# W5500_SCH.net
KiCad netlist of a schematic drawn in Altium Designer
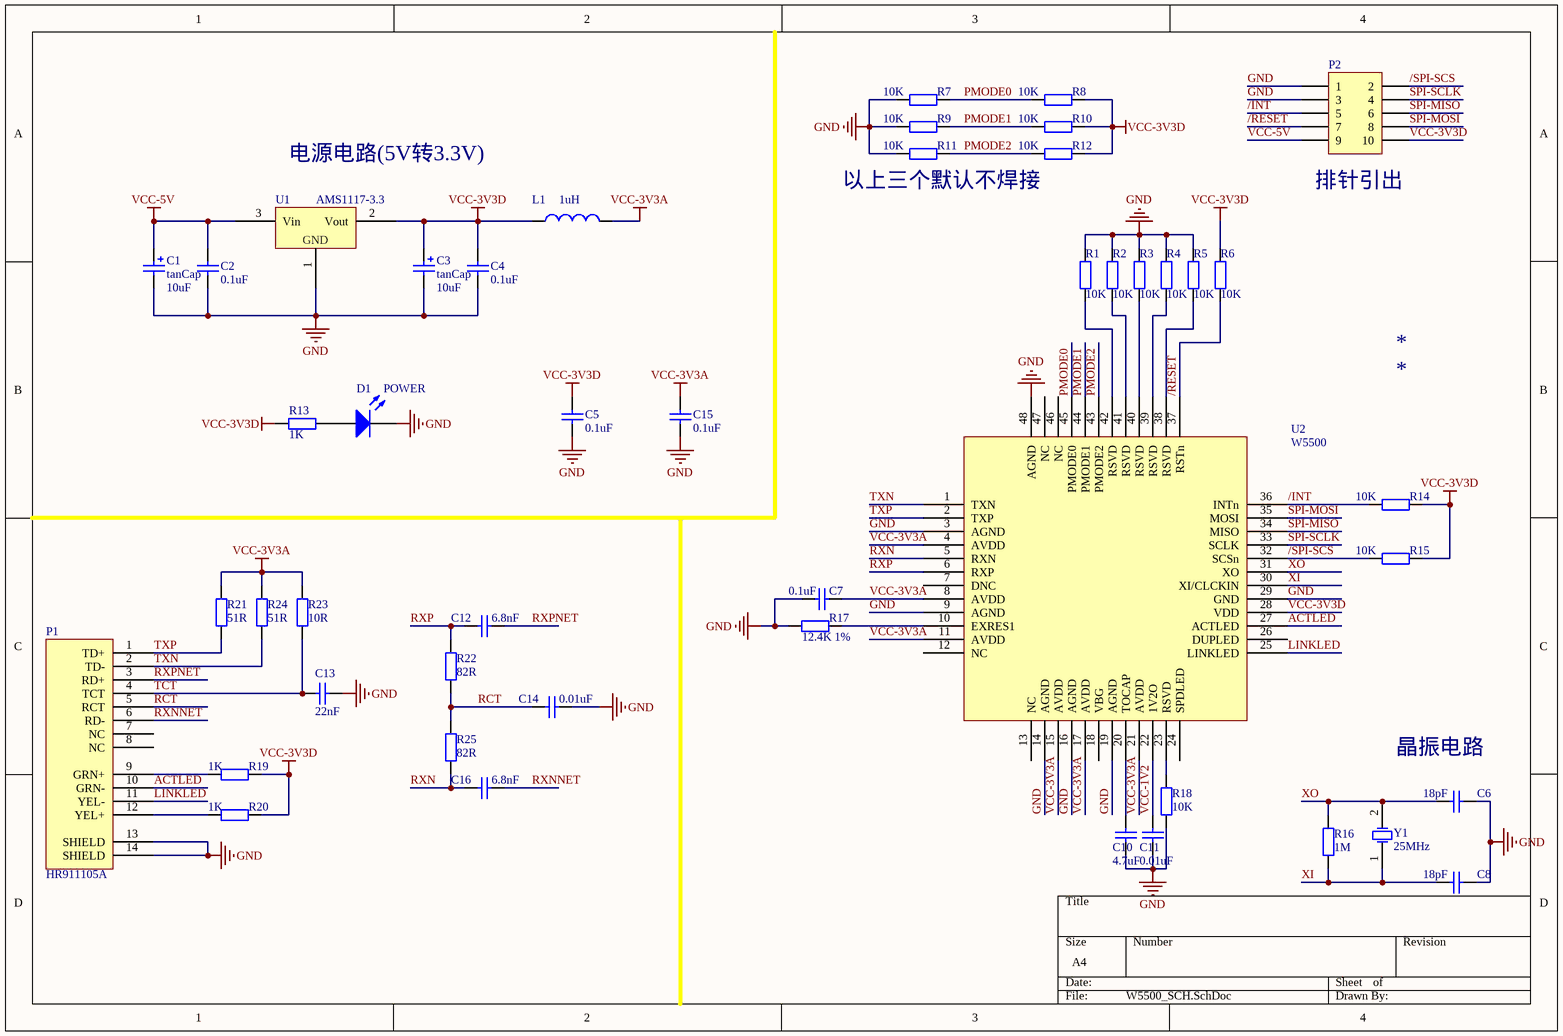
[diagram p0: W5500_SCH.SchDoc]

(export (version "E")
  (design (tool "Eeschema 10.0.6"))
  (components
    (comp (ref "C1")
      (value "tanCap")
      (footprint "C1206")
      (description "Polarized Capacitor (Axial)")
      (fields (field (name "ALTIUM_VALUE") "10uF") (field (name "PUBLISHER") "Altium Limited"))
      (libsource (lib "Miscellaneous Devices") (part "Cap Pol2"))
    )
    (comp (ref "C2")
      (value "0.1uF")
      (footprint "C0805")
      (description "Capacitor")
      (fields (field (name "Comment") "Cap") (field (name "PUBLISHER") "Altium Limited"))
      (libsource (lib "Miscellaneous Devices") (part "Cap"))
    )
    (comp (ref "C3")
      (value "tanCap")
      (footprint "C1206")
      (description "Polarized Capacitor (Axial)")
      (fields (field (name "ALTIUM_VALUE") "10uF") (field (name "PUBLISHER") "Altium Limited"))
      (libsource (lib "Miscellaneous Devices") (part "Cap Pol2"))
    )
    (comp (ref "C4")
      (value "0.1uF")
      (footprint "C0805")
      (description "Capacitor")
      (fields (field (name "Comment") "Cap") (field (name "PUBLISHER") "Altium Limited"))
      (libsource (lib "Miscellaneous Devices") (part "Cap"))
    )
    (comp (ref "C5")
      (value "0.1uF")
      (footprint "C0805")
      (description "Capacitor")
      (fields (field (name "Comment") "Cap") (field (name "PUBLISHER") "Altium Limited"))
      (libsource (lib "Miscellaneous Devices") (part "Cap"))
    )
    (comp (ref "C6")
      (value "18pF")
      (footprint "C0805")
      (description "Capacitor")
      (fields (field (name "Comment") "Cap") (field (name "PUBLISHER") "Altium Limited"))
      (libsource (lib "Miscellaneous Devices") (part "Cap"))
    )
    (comp (ref "C7")
      (value "0.1uF")
      (footprint "C0805")
      (description "Capacitor")
      (fields (field (name "Comment") "Cap") (field (name "PUBLISHER") "Altium Limited"))
      (libsource (lib "Miscellaneous Devices") (part "Cap"))
    )
    (comp (ref "C8")
      (value "18pF")
      (footprint "C0805")
      (description "Capacitor")
      (fields (field (name "Comment") "Cap") (field (name "PUBLISHER") "Altium Limited"))
      (libsource (lib "Miscellaneous Devices") (part "Cap"))
    )
    (comp (ref "C10")
      (value "4.7uF")
      (footprint "C0805")
      (description "Capacitor")
      (fields (field (name "Comment") "Cap") (field (name "PUBLISHER") "Altium Limited"))
      (libsource (lib "Miscellaneous Devices") (part "Cap"))
    )
    (comp (ref "C11")
      (value "0.01uF")
      (footprint "C0805")
      (description "Capacitor")
      (fields (field (name "Comment") "Cap") (field (name "PUBLISHER") "Altium Limited"))
      (libsource (lib "Miscellaneous Devices") (part "Cap"))
    )
    (comp (ref "C12")
      (value "6.8nF")
      (footprint "C0805")
      (description "Capacitor")
      (fields (field (name "Comment") "Cap") (field (name "PUBLISHER") "Altium Limited"))
      (libsource (lib "Miscellaneous Devices") (part "Cap"))
    )
    (comp (ref "C13")
      (value "22nF")
      (footprint "C0805")
      (description "Capacitor")
      (fields (field (name "Comment") "Cap") (field (name "PUBLISHER") "Altium Limited"))
      (libsource (lib "Miscellaneous Devices") (part "Cap"))
    )
    (comp (ref "C14")
      (value "0.01uF")
      (footprint "C0805")
      (description "Capacitor")
      (fields (field (name "Comment") "Cap") (field (name "PUBLISHER") "Altium Limited"))
      (libsource (lib "Miscellaneous Devices") (part "Cap"))
    )
    (comp (ref "C15")
      (value "0.1uF")
      (footprint "C0805")
      (description "Capacitor")
      (fields (field (name "Comment") "Cap") (field (name "PUBLISHER") "Altium Limited"))
      (libsource (lib "Miscellaneous Devices") (part "Cap"))
    )
    (comp (ref "C16")
      (value "6.8nF")
      (footprint "C0805")
      (description "Capacitor")
      (fields (field (name "Comment") "Cap") (field (name "PUBLISHER") "Altium Limited"))
      (libsource (lib "Miscellaneous Devices") (part "Cap"))
    )
    (comp (ref "D1")
      (value "POWER")
      (footprint "C0805")
      (description "Typical INFRARED GaAs LED")
      (fields (field (name "PUBLISHER") "Altium Limited"))
      (libsource (lib "Miscellaneous Devices") (part "LED0"))
    )
    (comp (ref "L1")
      (value "1uH")
      (footprint "C0805")
      (description "Inductor")
      (fields (field (name "PUBLISHER") "Altium Limited"))
      (libsource (lib "Miscellaneous Devices") (part "Inductor"))
    )
    (comp (ref "P1")
      (value "HR911105A")
      (footprint "HR911105A")
      (description "RJ45插座")
      (libsource (lib "W5500_SCH") (part "HR911105A"))
    )
    (comp (ref "P2")
      (value "排针引出")
      (footprint "HDR2X5")
      (description "Header, 5-Pin, Dual row")
      (fields (field (name "PUBLISHER") "Altium Limited"))
      (libsource (lib "Miscellaneous Connectors") (part "Header 5X2"))
    )
    (comp (ref "R1")
      (value "10K")
      (footprint "C0805")
      (description "Resistor")
      (fields (field (name "Comment") "Res2") (field (name "PUBLISHER") "Altium Limited"))
      (libsource (lib "Miscellaneous Devices") (part "Res2"))
    )
    (comp (ref "R2")
      (value "10K")
      (footprint "C0805")
      (description "Resistor")
      (fields (field (name "Comment") "Res2") (field (name "PUBLISHER") "Altium Limited"))
      (libsource (lib "Miscellaneous Devices") (part "Res2"))
    )
    (comp (ref "R3")
      (value "10K")
      (footprint "C0805")
      (description "Resistor")
      (fields (field (name "Comment") "Res2") (field (name "PUBLISHER") "Altium Limited"))
      (libsource (lib "Miscellaneous Devices") (part "Res2"))
    )
    (comp (ref "R4")
      (value "10K")
      (footprint "C0805")
      (description "Resistor")
      (fields (field (name "Comment") "Res2") (field (name "PUBLISHER") "Altium Limited"))
      (libsource (lib "Miscellaneous Devices") (part "Res2"))
    )
    (comp (ref "R5")
      (value "10K")
      (footprint "C0805")
      (description "Resistor")
      (fields (field (name "Comment") "Res2") (field (name "PUBLISHER") "Altium Limited"))
      (libsource (lib "Miscellaneous Devices") (part "Res2"))
    )
    (comp (ref "R6")
      (value "10K")
      (footprint "C0805")
      (description "Resistor")
      (fields (field (name "Comment") "Res2") (field (name "PUBLISHER") "Altium Limited"))
      (libsource (lib "Miscellaneous Devices") (part "Res2"))
    )
    (comp (ref "R7")
      (value "10K")
      (footprint "C0805")
      (description "Resistor")
      (fields (field (name "Comment") "Res2") (field (name "PUBLISHER") "Altium Limited"))
      (libsource (lib "") (part "Res2_2"))
    )
    (comp (ref "R8")
      (value "10K")
      (footprint "C0805")
      (description "Resistor")
      (fields (field (name "Comment") "Res2") (field (name "PUBLISHER") "Altium Limited"))
      (libsource (lib "") (part "Res2_2"))
    )
    (comp (ref "R9")
      (value "10K")
      (footprint "C0805")
      (description "Resistor")
      (fields (field (name "Comment") "Res2") (field (name "PUBLISHER") "Altium Limited"))
      (libsource (lib "") (part "Res2_2"))
    )
    (comp (ref "R10")
      (value "10K")
      (footprint "C0805")
      (description "Resistor")
      (fields (field (name "Comment") "Res2") (field (name "PUBLISHER") "Altium Limited"))
      (libsource (lib "") (part "Res2_2"))
    )
    (comp (ref "R11")
      (value "10K")
      (footprint "C0805")
      (description "Resistor")
      (fields (field (name "Comment") "Res2") (field (name "PUBLISHER") "Altium Limited"))
      (libsource (lib "") (part "Res2_2"))
    )
    (comp (ref "R12")
      (value "10K")
      (footprint "C0805")
      (description "Resistor")
      (fields (field (name "Comment") "Res2") (field (name "PUBLISHER") "Altium Limited"))
      (libsource (lib "") (part "Res2_2"))
    )
    (comp (ref "R13")
      (value "1K")
      (footprint "C0805")
      (description "Resistor")
      (fields (field (name "Comment") "Res2") (field (name "PUBLISHER") "Altium Limited"))
      (libsource (lib "") (part "Res2_3"))
    )
    (comp (ref "R14")
      (value "10K")
      (footprint "C0805")
      (description "Resistor")
      (fields (field (name "Comment") "Res2") (field (name "PUBLISHER") "Altium Limited"))
      (libsource (lib "") (part "Res2_2"))
    )
    (comp (ref "R15")
      (value "10K")
      (footprint "C0805")
      (description "Resistor")
      (fields (field (name "Comment") "Res2") (field (name "PUBLISHER") "Altium Limited"))
      (libsource (lib "") (part "Res2_2"))
    )
    (comp (ref "R16")
      (value "1M")
      (footprint "C0805")
      (description "Resistor")
      (fields (field (name "Comment") "Res2") (field (name "PUBLISHER") "Altium Limited"))
      (libsource (lib "Miscellaneous Devices") (part "Res2"))
    )
    (comp (ref "R17")
      (value "12.4K 1%")
      (footprint "C0805")
      (description "Resistor")
      (fields (field (name "Comment") "Res2") (field (name "PUBLISHER") "Altium Limited"))
      (libsource (lib "") (part "Res2_2"))
    )
    (comp (ref "R18")
      (value "10K")
      (footprint "C0805")
      (description "Resistor")
      (fields (field (name "Comment") "Res2") (field (name "PUBLISHER") "Altium Limited"))
      (libsource (lib "Miscellaneous Devices") (part "Res2"))
    )
    (comp (ref "R19")
      (value "1K")
      (footprint "C0805")
      (description "Resistor")
      (fields (field (name "Comment") "Res2") (field (name "PUBLISHER") "Altium Limited"))
      (libsource (lib "") (part "Res2_3"))
    )
    (comp (ref "R20")
      (value "1K")
      (footprint "C0805")
      (description "Resistor")
      (fields (field (name "Comment") "Res2") (field (name "PUBLISHER") "Altium Limited"))
      (libsource (lib "") (part "Res2_3"))
    )
    (comp (ref "R21")
      (value "51R")
      (footprint "C0805")
      (description "Resistor")
      (fields (field (name "Comment") "Res2") (field (name "PUBLISHER") "Altium Limited"))
      (libsource (lib "") (part "Res2_1"))
    )
    (comp (ref "R22")
      (value "82R")
      (footprint "C0805")
      (description "Resistor")
      (fields (field (name "Comment") "Res2") (field (name "PUBLISHER") "Altium Limited"))
      (libsource (lib "Miscellaneous Devices") (part "Res2"))
    )
    (comp (ref "R23")
      (value "10R")
      (footprint "C0805")
      (description "Resistor")
      (fields (field (name "Comment") "Res2") (field (name "PUBLISHER") "Altium Limited"))
      (libsource (lib "") (part "Res2_1"))
    )
    (comp (ref "R24")
      (value "51R")
      (footprint "C0805")
      (description "Resistor")
      (fields (field (name "Comment") "Res2") (field (name "PUBLISHER") "Altium Limited"))
      (libsource (lib "") (part "Res2_1"))
    )
    (comp (ref "R25")
      (value "82R")
      (footprint "C0805")
      (description "Resistor")
      (fields (field (name "Comment") "Res2") (field (name "PUBLISHER") "Altium Limited"))
      (libsource (lib "Miscellaneous Devices") (part "Res2"))
    )
    (comp (ref "U1")
      (value "AMS1117-3.3")
      (footprint "SOT223_M")
      (description "AMS1117-")
      (libsource (lib "qyh") (part "AMS1117"))
    )
    (comp (ref "U2")
      (value "W5500")
      (footprint "LQFP48")
      (description "W5500以太网芯片")
      (libsource (lib "W5500_SCH") (part "W5500"))
    )
    (comp (ref "Y1")
      (value "25MHz")
      (footprint "XTAL-HC49")
      (description "Crystal Oscillator")
      (fields (field (name "PUBLISHER") "Altium Limited"))
      (libsource (lib "Miscellaneous Devices") (part "XTAL"))
    )
  )
  (nets
    (net (code "1") (name "/ACTLED") (class "Default")
      (node (ref "P1") (pin "10") (pinfunction "GRN-_10") (pintype "passive"))
      (node (ref "U2") (pin "27") (pinfunction "ACTLED_27") (pintype "passive"))
    )
    (net (code "2") (name "/LINKLED") (class "Default")
      (node (ref "P1") (pin "11") (pinfunction "YEL-_11") (pintype "passive"))
      (node (ref "U2") (pin "25") (pinfunction "LINKLED_25") (pintype "passive"))
    )
    (net (code "3") (name "/PMODE0") (class "Default")
      (node (ref "R7") (pin "2") (pinfunction "2_2") (pintype "passive"))
      (node (ref "R8") (pin "1") (pinfunction "1_1") (pintype "passive"))
      (node (ref "U2") (pin "45") (pinfunction "PMODE0_45") (pintype "passive"))
    )
    (net (code "4") (name "/PMODE1") (class "Default")
      (node (ref "R10") (pin "1") (pinfunction "1_1") (pintype "passive"))
      (node (ref "R9") (pin "2") (pinfunction "2_2") (pintype "passive"))
      (node (ref "U2") (pin "44") (pinfunction "PMODE1_44") (pintype "passive"))
    )
    (net (code "5") (name "/PMODE2") (class "Default")
      (node (ref "R11") (pin "2") (pinfunction "2_2") (pintype "passive"))
      (node (ref "R12") (pin "1") (pinfunction "1_1") (pintype "passive"))
      (node (ref "U2") (pin "43") (pinfunction "PMODE2_43") (pintype "passive"))
    )
    (net (code "6") (name "/RCT") (class "Default")
      (node (ref "C14") (pin "2") (pinfunction "2_2") (pintype "passive"))
      (node (ref "P1") (pin "5") (pinfunction "RCT_5") (pintype "passive"))
      (node (ref "R22") (pin "1") (pinfunction "1_1") (pintype "passive"))
      (node (ref "R25") (pin "2") (pinfunction "2_2") (pintype "passive"))
    )
    (net (code "7") (name "/RXN") (class "Default")
      (node (ref "C16") (pin "2") (pinfunction "2_2") (pintype "passive"))
      (node (ref "R25") (pin "1") (pinfunction "1_1") (pintype "passive"))
      (node (ref "U2") (pin "5") (pinfunction "RXN_5") (pintype "passive"))
    )
    (net (code "8") (name "/RXNNET") (class "Default")
      (node (ref "C16") (pin "1") (pinfunction "1_1") (pintype "passive"))
      (node (ref "P1") (pin "6") (pinfunction "RD-_6") (pintype "passive"))
    )
    (net (code "9") (name "/RXP") (class "Default")
      (node (ref "C12") (pin "2") (pinfunction "2_2") (pintype "passive"))
      (node (ref "R22") (pin "2") (pinfunction "2_2") (pintype "passive"))
      (node (ref "U2") (pin "6") (pinfunction "RXP_6") (pintype "passive"))
    )
    (net (code "10") (name "/RXPNET") (class "Default")
      (node (ref "C12") (pin "1") (pinfunction "1_1") (pintype "passive"))
      (node (ref "P1") (pin "3") (pinfunction "RD+_3") (pintype "passive"))
    )
    (net (code "11") (name "/SPI-MISO") (class "Default")
      (node (ref "P2") (pin "6") (pinfunction "6_6") (pintype "passive"))
      (node (ref "U2") (pin "34") (pinfunction "MISO_34") (pintype "passive"))
    )
    (net (code "12") (name "/SPI-MOSI") (class "Default")
      (node (ref "P2") (pin "8") (pinfunction "8_8") (pintype "passive"))
      (node (ref "U2") (pin "35") (pinfunction "MOSI_35") (pintype "passive"))
    )
    (net (code "13") (name "/SPI-SCLK") (class "Default")
      (node (ref "P2") (pin "4") (pinfunction "4_4") (pintype "passive"))
      (node (ref "U2") (pin "33") (pinfunction "SCLK_33") (pintype "passive"))
    )
    (net (code "14") (name "/TCT") (class "Default")
      (node (ref "C13") (pin "1") (pinfunction "1_1") (pintype "passive"))
      (node (ref "P1") (pin "4") (pinfunction "TCT_4") (pintype "passive"))
      (node (ref "R23") (pin "2") (pinfunction "2_2") (pintype "passive"))
    )
    (net (code "15") (name "/TXN") (class "Default")
      (node (ref "P1") (pin "2") (pinfunction "TD-_2") (pintype "passive"))
      (node (ref "R24") (pin "2") (pinfunction "2_2") (pintype "passive"))
      (node (ref "U2") (pin "1") (pinfunction "TXN_1") (pintype "passive"))
    )
    (net (code "16") (name "/TXP") (class "Default")
      (node (ref "P1") (pin "1") (pinfunction "TD+_1") (pintype "passive"))
      (node (ref "R21") (pin "2") (pinfunction "2_2") (pintype "passive"))
      (node (ref "U2") (pin "2") (pinfunction "TXP_2") (pintype "passive"))
    )
    (net (code "17") (name "/VCC-1V2") (class "Default")
      (node (ref "C11") (pin "1") (pinfunction "1_1") (pintype "passive"))
      (node (ref "U2") (pin "22") (pinfunction "1V2O_22") (pintype "passive"))
    )
    (net (code "18") (name "/XI") (class "Default")
      (node (ref "C8") (pin "2") (pinfunction "2_2") (pintype "passive"))
      (node (ref "R16") (pin "1") (pinfunction "1_1") (pintype "passive"))
      (node (ref "U2") (pin "30") (pinfunction "XI/CLCKIN_30") (pintype "passive"))
      (node (ref "Y1") (pin "1") (pinfunction "OSC1_1") (pintype "passive"))
    )
    (net (code "19") (name "/XO") (class "Default")
      (node (ref "C6") (pin "2") (pinfunction "2_2") (pintype "passive"))
      (node (ref "R16") (pin "2") (pinfunction "2_2") (pintype "passive"))
      (node (ref "U2") (pin "31") (pinfunction "XO_31") (pintype "passive"))
      (node (ref "Y1") (pin "2") (pinfunction "OSC2_2") (pintype "passive"))
    )
    (net (code "20") (name "/{slash}INT") (class "Default")
      (node (ref "P2") (pin "5") (pinfunction "5_5") (pintype "passive"))
      (node (ref "R14") (pin "1") (pinfunction "1_1") (pintype "passive"))
      (node (ref "U2") (pin "36") (pinfunction "INTn_36") (pintype "passive"))
    )
    (net (code "21") (name "/{slash}RESET") (class "Default")
      (node (ref "P2") (pin "7") (pinfunction "7_7") (pintype "passive"))
      (node (ref "R6") (pin "1") (pinfunction "1_1") (pintype "passive"))
      (node (ref "U2") (pin "37") (pinfunction "RSTn_37") (pintype "passive"))
    )
    (net (code "22") (name "/{slash}SPI-SCS") (class "Default")
      (node (ref "P2") (pin "2") (pinfunction "2_2") (pintype "passive"))
      (node (ref "R15") (pin "1") (pinfunction "1_1") (pintype "passive"))
      (node (ref "U2") (pin "32") (pinfunction "SCSn_32") (pintype "passive"))
    )
    (net (code "23") (name "GND") (class "Default")
      (node (ref "C1") (pin "2") (pinfunction "2_2") (pintype "passive"))
      (node (ref "C10") (pin "2") (pinfunction "2_2") (pintype "passive"))
      (node (ref "C11") (pin "2") (pinfunction "2_2") (pintype "passive"))
      (node (ref "C13") (pin "2") (pinfunction "2_2") (pintype "passive"))
      (node (ref "C14") (pin "1") (pinfunction "1_1") (pintype "passive"))
      (node (ref "C15") (pin "1") (pinfunction "1_1") (pintype "passive"))
      (node (ref "C2") (pin "2") (pinfunction "2_2") (pintype "passive"))
      (node (ref "C3") (pin "2") (pinfunction "2_2") (pintype "passive"))
      (node (ref "C4") (pin "2") (pinfunction "2_2") (pintype "passive"))
      (node (ref "C5") (pin "2") (pinfunction "2_2") (pintype "passive"))
      (node (ref "C6") (pin "1") (pinfunction "1_1") (pintype "passive"))
      (node (ref "C7") (pin "2") (pinfunction "2_2") (pintype "passive"))
      (node (ref "C8") (pin "1") (pinfunction "1_1") (pintype "passive"))
      (node (ref "D1") (pin "2") (pinfunction "K_2") (pintype "passive"))
      (node (ref "P1") (pin "13") (pinfunction "SHIELD_13") (pintype "passive"))
      (node (ref "P1") (pin "14") (pinfunction "SHIELD_14") (pintype "passive"))
      (node (ref "P2") (pin "1") (pinfunction "1_1") (pintype "passive"))
      (node (ref "P2") (pin "3") (pinfunction "3_3") (pintype "passive"))
      (node (ref "R1") (pin "2") (pinfunction "2_2") (pintype "passive"))
      (node (ref "R11") (pin "1") (pinfunction "1_1") (pintype "passive"))
      (node (ref "R17") (pin "1") (pinfunction "1_1") (pintype "passive"))
      (node (ref "R18") (pin "1") (pinfunction "1_1") (pintype "passive"))
      (node (ref "R2") (pin "2") (pinfunction "2_2") (pintype "passive"))
      (node (ref "R3") (pin "2") (pinfunction "2_2") (pintype "passive"))
      (node (ref "R4") (pin "2") (pinfunction "2_2") (pintype "passive"))
      (node (ref "R5") (pin "2") (pinfunction "2_2") (pintype "passive"))
      (node (ref "R7") (pin "1") (pinfunction "1_1") (pintype "passive"))
      (node (ref "R9") (pin "1") (pinfunction "1_1") (pintype "passive"))
      (node (ref "U1") (pin "1") (pinfunction "GND_1") (pintype "passive"))
      (node (ref "U2") (pin "14") (pinfunction "AGND_14") (pintype "passive"))
      (node (ref "U2") (pin "16") (pinfunction "AGND_16") (pintype "passive"))
      (node (ref "U2") (pin "19") (pinfunction "AGND_19") (pintype "passive"))
      (node (ref "U2") (pin "29") (pinfunction "GND_29") (pintype "passive"))
      (node (ref "U2") (pin "3") (pinfunction "AGND_3") (pintype "passive"))
      (node (ref "U2") (pin "48") (pinfunction "AGND_48") (pintype "passive"))
      (node (ref "U2") (pin "9") (pinfunction "AGND_9") (pintype "passive"))
    )
    (net (code "24") (name "Net-(D1-A)") (class "Default")
      (node (ref "D1") (pin "1") (pinfunction "A_1") (pintype "passive"))
      (node (ref "R13") (pin "1") (pinfunction "1_1") (pintype "passive"))
    )
    (net (code "25") (name "Net-(P1-GRN+)") (class "Default")
      (node (ref "P1") (pin "9") (pinfunction "GRN+_9") (pintype "passive"))
      (node (ref "R19") (pin "2") (pinfunction "2_2") (pintype "passive"))
    )
    (net (code "26") (name "Net-(P1-YEL+)") (class "Default")
      (node (ref "P1") (pin "12") (pinfunction "YEL+_12") (pintype "passive"))
      (node (ref "R20") (pin "2") (pinfunction "2_2") (pintype "passive"))
    )
    (net (code "27") (name "Net-(R1-Pad1)") (class "Default")
      (node (ref "R1") (pin "1") (pinfunction "1_1") (pintype "passive"))
      (node (ref "U2") (pin "42") (pinfunction "RSVD_42") (pintype "passive"))
    )
    (net (code "28") (name "Net-(R2-Pad1)") (class "Default")
      (node (ref "R2") (pin "1") (pinfunction "1_1") (pintype "passive"))
      (node (ref "U2") (pin "41") (pinfunction "RSVD_41") (pintype "passive"))
    )
    (net (code "29") (name "Net-(R3-Pad1)") (class "Default")
      (node (ref "R3") (pin "1") (pinfunction "1_1") (pintype "passive"))
      (node (ref "U2") (pin "40") (pinfunction "RSVD_40") (pintype "passive"))
    )
    (net (code "30") (name "Net-(R4-Pad1)") (class "Default")
      (node (ref "R4") (pin "1") (pinfunction "1_1") (pintype "passive"))
      (node (ref "U2") (pin "39") (pinfunction "RSVD_39") (pintype "passive"))
    )
    (net (code "31") (name "Net-(R5-Pad1)") (class "Default")
      (node (ref "R5") (pin "1") (pinfunction "1_1") (pintype "passive"))
      (node (ref "U2") (pin "38") (pinfunction "RSVD_38") (pintype "passive"))
    )
    (net (code "32") (name "Net-(R18-Pad2)") (class "Default")
      (node (ref "R18") (pin "2") (pinfunction "2_2") (pintype "passive"))
      (node (ref "U2") (pin "23") (pinfunction "RSVD_23") (pintype "passive"))
    )
    (net (code "33") (name "Net-(U2-EXRES1)") (class "Default")
      (node (ref "R17") (pin "2") (pinfunction "2_2") (pintype "passive"))
      (node (ref "U2") (pin "10") (pinfunction "EXRES1_10") (pintype "passive"))
    )
    (net (code "34") (name "Net-(U2-TOCAP)") (class "Default")
      (node (ref "C10") (pin "1") (pinfunction "1_1") (pintype "passive"))
      (node (ref "U2") (pin "20") (pinfunction "TOCAP_20") (pintype "passive"))
    )
    (net (code "35") (name "VCC-3V3A") (class "Default")
      (node (ref "C15") (pin "2") (pinfunction "2_2") (pintype "passive"))
      (node (ref "C7") (pin "1") (pinfunction "1_1") (pintype "passive"))
      (node (ref "L1") (pin "2") (pinfunction "2_2") (pintype "passive"))
      (node (ref "R21") (pin "1") (pinfunction "1_1") (pintype "passive"))
      (node (ref "R23") (pin "1") (pinfunction "1_1") (pintype "passive"))
      (node (ref "R24") (pin "1") (pinfunction "1_1") (pintype "passive"))
      (node (ref "U2") (pin "11") (pinfunction "AVDD_11") (pintype "passive"))
      (node (ref "U2") (pin "15") (pinfunction "AVDD_15") (pintype "passive"))
      (node (ref "U2") (pin "17") (pinfunction "AVDD_17") (pintype "passive"))
      (node (ref "U2") (pin "21") (pinfunction "AVDD_21") (pintype "passive"))
      (node (ref "U2") (pin "4") (pinfunction "AVDD_4") (pintype "passive"))
      (node (ref "U2") (pin "8") (pinfunction "AVDD_8") (pintype "passive"))
    )
    (net (code "36") (name "VCC-3V3D") (class "Default")
      (node (ref "C3") (pin "1") (pinfunction "1_1") (pintype "passive"))
      (node (ref "C4") (pin "1") (pinfunction "1_1") (pintype "passive"))
      (node (ref "C5") (pin "1") (pinfunction "1_1") (pintype "passive"))
      (node (ref "L1") (pin "1") (pinfunction "1_1") (pintype "passive"))
      (node (ref "P2") (pin "10") (pinfunction "10_10") (pintype "passive"))
      (node (ref "R10") (pin "2") (pinfunction "2_2") (pintype "passive"))
      (node (ref "R12") (pin "2") (pinfunction "2_2") (pintype "passive"))
      (node (ref "R13") (pin "2") (pinfunction "2_2") (pintype "passive"))
      (node (ref "R14") (pin "2") (pinfunction "2_2") (pintype "passive"))
      (node (ref "R15") (pin "2") (pinfunction "2_2") (pintype "passive"))
      (node (ref "R19") (pin "1") (pinfunction "1_1") (pintype "passive"))
      (node (ref "R20") (pin "1") (pinfunction "1_1") (pintype "passive"))
      (node (ref "R6") (pin "2") (pinfunction "2_2") (pintype "passive"))
      (node (ref "R8") (pin "2") (pinfunction "2_2") (pintype "passive"))
      (node (ref "U1") (pin "2") (pinfunction "Vout_2") (pintype "passive"))
      (node (ref "U2") (pin "28") (pinfunction "VDD_28") (pintype "passive"))
    )
    (net (code "37") (name "VCC-5V") (class "Default")
      (node (ref "C1") (pin "1") (pinfunction "1_1") (pintype "passive"))
      (node (ref "C2") (pin "1") (pinfunction "1_1") (pintype "passive"))
      (node (ref "P2") (pin "9") (pinfunction "9_9") (pintype "passive"))
      (node (ref "U1") (pin "3") (pinfunction "Vin_3") (pintype "passive"))
    )
    (net (code "38") (name "unconnected-(P1-NC-Pad7)") (class "Default")
      (node (ref "P1") (pin "7") (pinfunction "NC_7") (pintype "passive"))
    )
    (net (code "39") (name "unconnected-(P1-NC-Pad8)") (class "Default")
      (node (ref "P1") (pin "8") (pinfunction "NC_8") (pintype "passive"))
    )
    (net (code "40") (name "unconnected-(U2-DNC-Pad7)") (class "Default")
      (node (ref "U2") (pin "7") (pinfunction "DNC_7") (pintype "passive"))
    )
    (net (code "41") (name "unconnected-(U2-DUPLED-Pad26)") (class "Default")
      (node (ref "U2") (pin "26") (pinfunction "DUPLED_26") (pintype "passive"))
    )
    (net (code "42") (name "unconnected-(U2-NC-Pad12)") (class "Default")
      (node (ref "U2") (pin "12") (pinfunction "NC_12") (pintype "passive"))
    )
    (net (code "43") (name "unconnected-(U2-NC-Pad13)") (class "Default")
      (node (ref "U2") (pin "13") (pinfunction "NC_13") (pintype "passive"))
    )
    (net (code "44") (name "unconnected-(U2-NC-Pad46)") (class "Default")
      (node (ref "U2") (pin "46") (pinfunction "NC_46") (pintype "passive"))
    )
    (net (code "45") (name "unconnected-(U2-NC-Pad47)") (class "Default")
      (node (ref "U2") (pin "47") (pinfunction "NC_47") (pintype "passive"))
    )
    (net (code "46") (name "unconnected-(U2-SPDLED-Pad24)") (class "Default")
      (node (ref "U2") (pin "24") (pinfunction "SPDLED_24") (pintype "passive"))
    )
    (net (code "47") (name "unconnected-(U2-VBG-Pad18)") (class "Default")
      (node (ref "U2") (pin "18") (pinfunction "VBG_18") (pintype "passive"))
    )
  )
)
